# binaryspaceflower.net
KiCad netlist of a schematic drawn in EAGLE
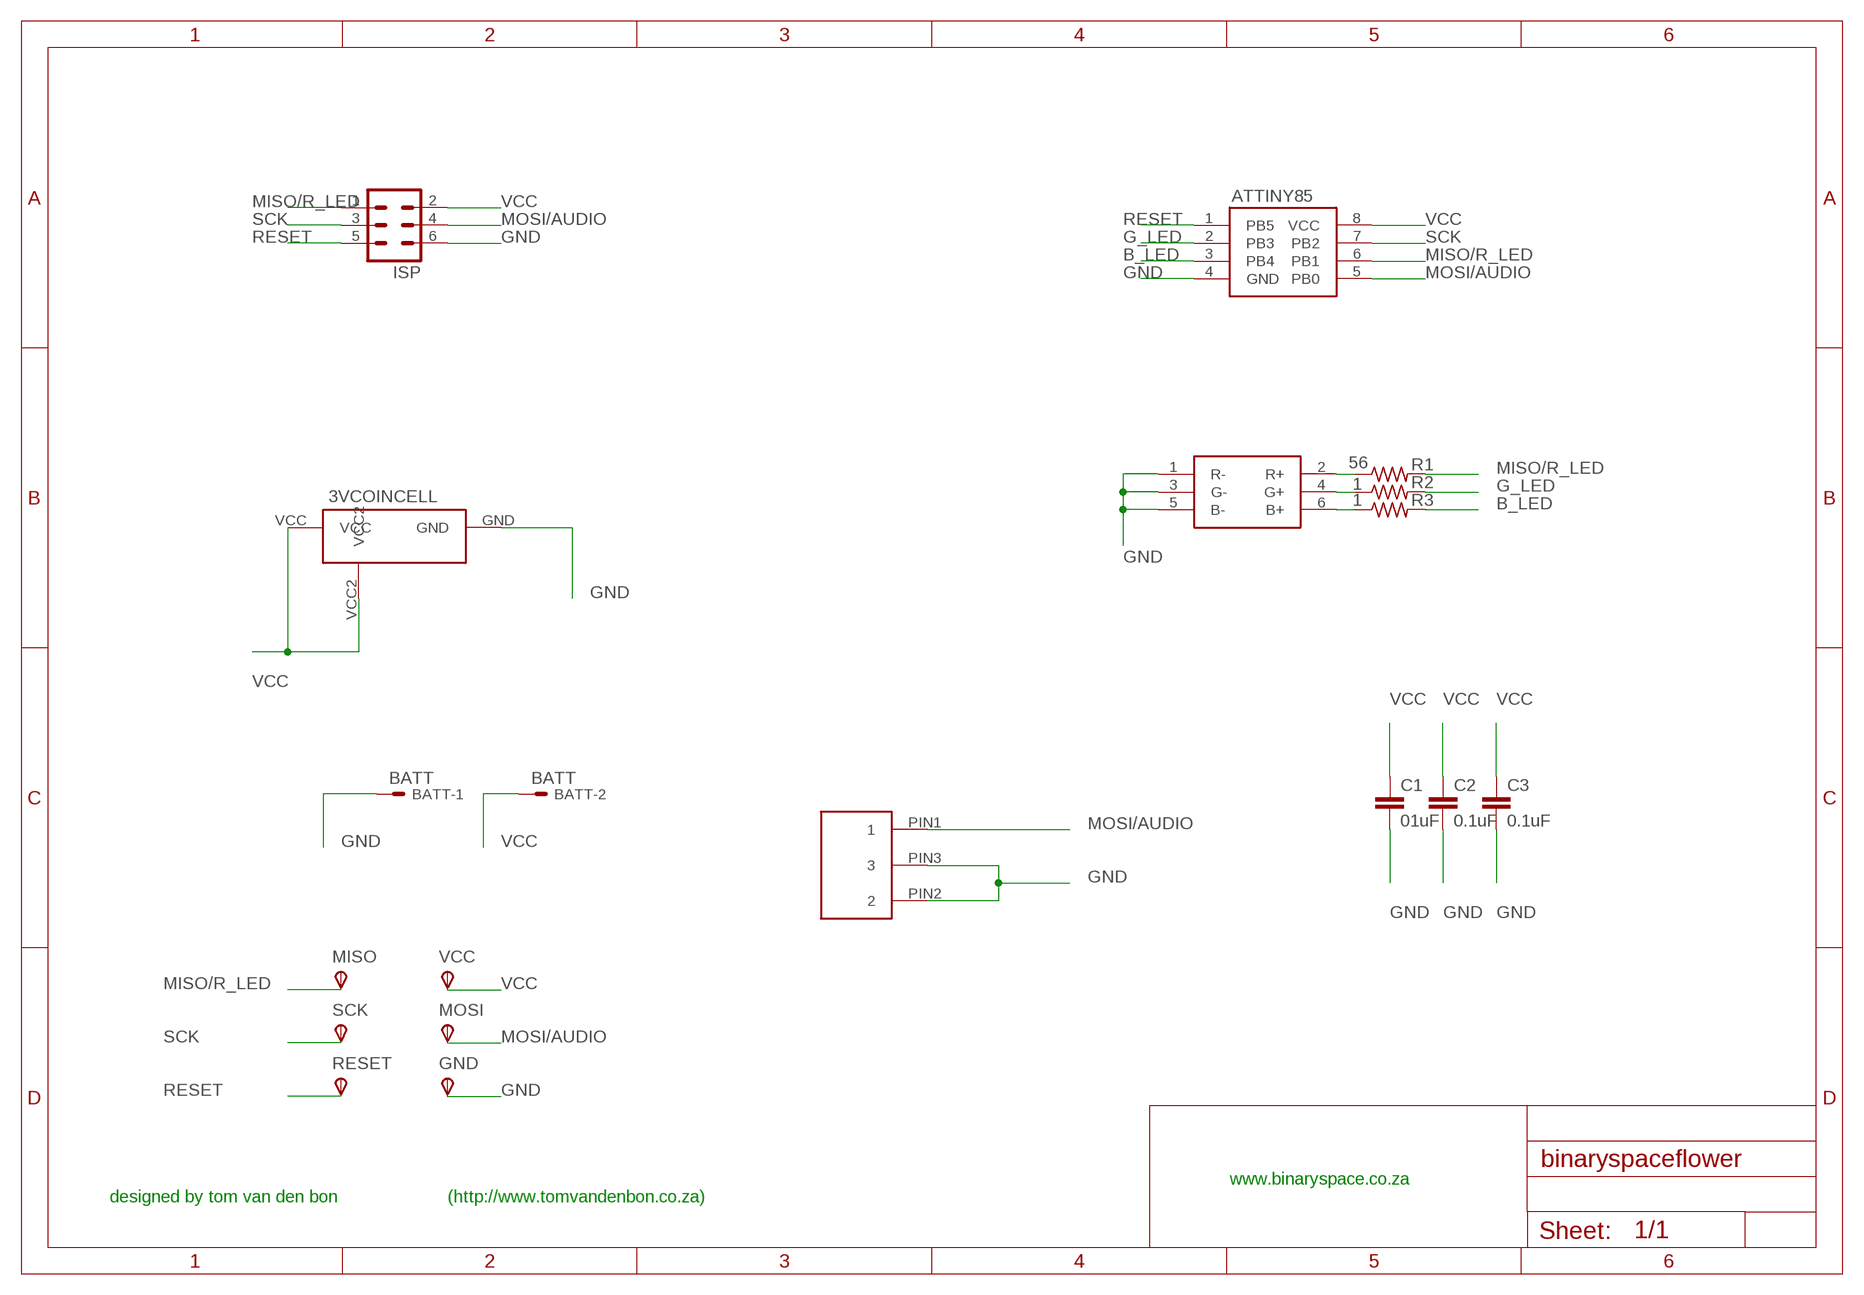
[diagram p0: schematic, sheet 1]

(export (version "E")
  (design (tool "Eeschema 10.0.6"))
  (components
    (comp (ref "3VCOINCELL")
      (value "SMD_COINCELL_HOLDERRS")
      (footprint "eagle-import:SMD_COINCELLHOLDER")
      (libsource (lib "eagle-import") (part "SMD_COINCELL_HOLDERRS"))
    )
    (comp (ref "ATTINY85")
      (value "ATTINY85ATTINY85")
      (footprint "eagle-import:SOIC-20")
      (libsource (lib "eagle-import") (part "ATTINY85ATTINY85"))
    )
    (comp (ref "BATT")
      (value "BATT")
      (footprint "eagle-import:332-02")
      (libsource (lib "eagle-import") (part "332-02"))
    )
    (comp (ref "C1")
      (value "01uF")
      (footprint "eagle-import:C0603")
      (libsource (lib "eagle-import") (part "C-EUC0603"))
    )
    (comp (ref "C2")
      (value "0.1uF")
      (footprint "eagle-import:C0603")
      (libsource (lib "eagle-import") (part "C-EUC0603"))
    )
    (comp (ref "C3")
      (value "0.1uF")
      (footprint "eagle-import:C0603")
      (libsource (lib "eagle-import") (part "C-EUC0603"))
    )
    (comp (ref "GND")
      (value "TPSTP09R")
      (footprint "eagle-import:TP09R")
      (libsource (lib "eagle-import") (part "TPSTP09R"))
    )
    (comp (ref "ISP")
      (value "MA03-2")
      (footprint "eagle-import:MA03-2")
      (libsource (lib "eagle-import") (part "MA03-2"))
    )
    (comp (ref "MISO")
      (value "TPSTP09R")
      (footprint "eagle-import:TP09R")
      (libsource (lib "eagle-import") (part "TPSTP09R"))
    )
    (comp (ref "MOSI")
      (value "TPSTP09R")
      (footprint "eagle-import:TP09R")
      (libsource (lib "eagle-import") (part "TPSTP09R"))
    )
    (comp (ref "R1")
      (value "56")
      (footprint "eagle-import:R0603")
      (libsource (lib "eagle-import") (part "R-US_R0603"))
    )
    (comp (ref "R2")
      (value "1")
      (footprint "eagle-import:R0603")
      (libsource (lib "eagle-import") (part "R-US_R0603"))
    )
    (comp (ref "R3")
      (value "1")
      (footprint "eagle-import:R0603")
      (libsource (lib "eagle-import") (part "R-US_R0603"))
    )
    (comp (ref "RESET")
      (value "TPSTP09R")
      (footprint "eagle-import:TP09R")
      (libsource (lib "eagle-import") (part "TPSTP09R"))
    )
    (comp (ref "SCK")
      (value "TPSTP09R")
      (footprint "eagle-import:TP09R")
      (libsource (lib "eagle-import") (part "TPSTP09R"))
    )
    (comp (ref "U$2")
      (value "RGB_SMD_LEDRS")
      (footprint "eagle-import:SMD_RGB_769-2996")
      (libsource (lib "eagle-import") (part "RGB_SMD_LEDRS"))
    )
    (comp (ref "U$3")
      (value "2.5MMAUDIOJACKMANTECH")
      (footprint "eagle-import:K3624")
      (libsource (lib "eagle-import") (part "2.5MMAUDIOJACKMANTECH"))
    )
    (comp (ref "VCC")
      (value "TPSTP09R")
      (footprint "eagle-import:TP09R")
      (libsource (lib "eagle-import") (part "TPSTP09R"))
    )
  )
  (nets
    (net (code "1") (name "/B_LED") (class "Default")
      (node (ref "ATTINY85") (pin "3") (pinfunction "PB4_3") (pintype "bidirectional"))
      (node (ref "R3") (pin "2") (pinfunction "2_2") (pintype "passive"))
    )
    (net (code "2") (name "/GND") (class "Default")
      (node (ref "3VCOINCELL") (pin "GND") (pinfunction "GND_GND") (pintype "bidirectional"))
      (node (ref "ATTINY85") (pin "4") (pinfunction "GND_4") (pintype "bidirectional"))
      (node (ref "BATT") (pin "1") (pinfunction "S_1") (pintype "passive"))
      (node (ref "C1") (pin "2") (pinfunction "2_2") (pintype "passive"))
      (node (ref "C2") (pin "2") (pinfunction "2_2") (pintype "passive"))
      (node (ref "C3") (pin "2") (pinfunction "2_2") (pintype "passive"))
      (node (ref "GND") (pin "TP") (pinfunction "PP_TP") (pintype "input"))
      (node (ref "ISP") (pin "6") (pinfunction "6_6") (pintype "passive"))
      (node (ref "U$2") (pin "1") (pinfunction "R-_1") (pintype "bidirectional"))
      (node (ref "U$2") (pin "3") (pinfunction "G-_3") (pintype "bidirectional"))
      (node (ref "U$2") (pin "5") (pinfunction "B-_5") (pintype "bidirectional"))
      (node (ref "U$3") (pin "PIN2") (pinfunction "2_PIN2") (pintype "bidirectional"))
      (node (ref "U$3") (pin "PIN3") (pinfunction "3_PIN3") (pintype "bidirectional"))
    )
    (net (code "3") (name "/G_LED") (class "Default")
      (node (ref "ATTINY85") (pin "2") (pinfunction "PB3_2") (pintype "bidirectional"))
      (node (ref "R2") (pin "2") (pinfunction "2_2") (pintype "passive"))
    )
    (net (code "4") (name "/MISO{slash}R_LED") (class "Default")
      (node (ref "ATTINY85") (pin "6") (pinfunction "PB1_6") (pintype "bidirectional"))
      (node (ref "ISP") (pin "1") (pinfunction "1_1") (pintype "passive"))
      (node (ref "MISO") (pin "TP") (pinfunction "PP_TP") (pintype "input"))
      (node (ref "R1") (pin "2") (pinfunction "2_2") (pintype "passive"))
    )
    (net (code "5") (name "/MOSI{slash}AUDIO") (class "Default")
      (node (ref "ATTINY85") (pin "5") (pinfunction "PB0_5") (pintype "bidirectional"))
      (node (ref "ISP") (pin "4") (pinfunction "4_4") (pintype "passive"))
      (node (ref "MOSI") (pin "TP") (pinfunction "PP_TP") (pintype "input"))
      (node (ref "U$3") (pin "PIN1") (pinfunction "1_PIN1") (pintype "bidirectional"))
    )
    (net (code "6") (name "/RESET") (class "Default")
      (node (ref "ATTINY85") (pin "1") (pinfunction "PB5_1") (pintype "bidirectional"))
      (node (ref "ISP") (pin "5") (pinfunction "5_5") (pintype "passive"))
      (node (ref "RESET") (pin "TP") (pinfunction "PP_TP") (pintype "input"))
    )
    (net (code "7") (name "/SCK") (class "Default")
      (node (ref "ATTINY85") (pin "7") (pinfunction "PB2_7") (pintype "bidirectional"))
      (node (ref "ISP") (pin "3") (pinfunction "3_3") (pintype "passive"))
      (node (ref "SCK") (pin "TP") (pinfunction "PP_TP") (pintype "input"))
    )
    (net (code "8") (name "/VCC") (class "Default")
      (node (ref "3VCOINCELL") (pin "VCC") (pinfunction "VCC_VCC") (pintype "bidirectional"))
      (node (ref "3VCOINCELL") (pin "VCC2") (pinfunction "VCC2_VCC2") (pintype "bidirectional"))
      (node (ref "ATTINY85") (pin "8") (pinfunction "VCC_8") (pintype "bidirectional"))
      (node (ref "BATT") (pin "2") (pinfunction "S_2") (pintype "passive"))
      (node (ref "C1") (pin "1") (pinfunction "1_1") (pintype "passive"))
      (node (ref "C2") (pin "1") (pinfunction "1_1") (pintype "passive"))
      (node (ref "C3") (pin "1") (pinfunction "1_1") (pintype "passive"))
      (node (ref "ISP") (pin "2") (pinfunction "2_2") (pintype "passive"))
      (node (ref "VCC") (pin "TP") (pinfunction "PP_TP") (pintype "input"))
    )
    (net (code "9") (name "Net-(U$2-B+)") (class "Default")
      (node (ref "R3") (pin "1") (pinfunction "1_1") (pintype "passive"))
      (node (ref "U$2") (pin "6") (pinfunction "B+_6") (pintype "bidirectional"))
    )
    (net (code "10") (name "Net-(U$2-G+)") (class "Default")
      (node (ref "R2") (pin "1") (pinfunction "1_1") (pintype "passive"))
      (node (ref "U$2") (pin "4") (pinfunction "G+_4") (pintype "bidirectional"))
    )
    (net (code "11") (name "Net-(U$2-R+)") (class "Default")
      (node (ref "R1") (pin "1") (pinfunction "1_1") (pintype "passive"))
      (node (ref "U$2") (pin "2") (pinfunction "R+_2") (pintype "bidirectional"))
    )
  )
)
